# Schematic_4_22_12.net
KiCad netlist of a schematic drawn in EAGLE
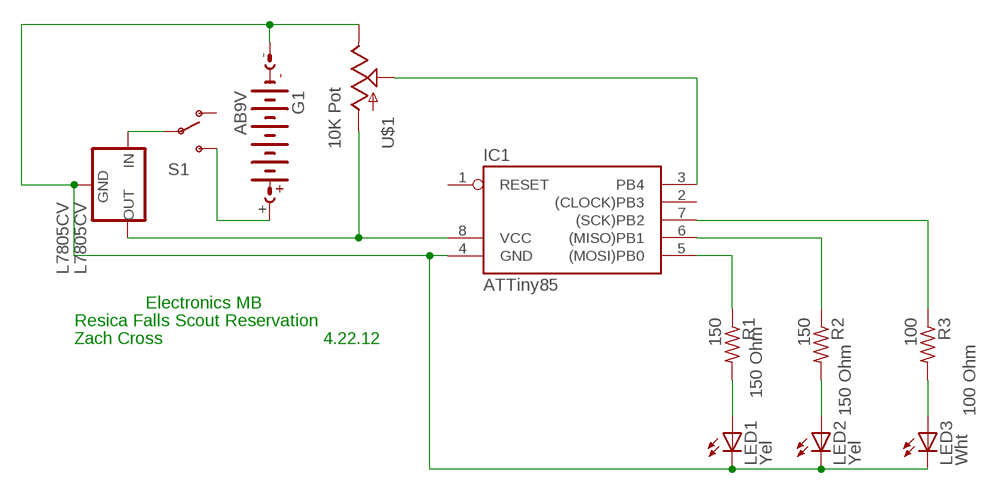
[diagram p0: schematic, sheet 1]

(export (version "E")
  (design (tool "Eeschema 10.0.6"))
  (components
    (comp (ref "G1")
      (value "AB9V")
      (footprint "eagle-import:AB9V")
      (libsource (lib "eagle-import") (part "AB9V"))
    )
    (comp (ref "IC1")
      (value "ATTiny85")
      (footprint "eagle-import:DIL08")
      (libsource (lib "eagle-import") (part "TINY22P"))
    )
    (comp (ref "L7805CV")
      (value "L7805CV")
      (footprint "eagle-import:78XXL")
      (libsource (lib "eagle-import") (part "V_REG_78XXSIDE"))
    )
    (comp (ref "LED1")
      (value "Yel")
      (footprint "eagle-import:LED5MM")
      (fields (field (name "COLOR") "Yellow"))
      (libsource (lib "eagle-import") (part "LED5MM"))
    )
    (comp (ref "LED2")
      (value "Yel")
      (footprint "eagle-import:LED5MM")
      (fields (field (name "COLOR") "Yellow"))
      (libsource (lib "eagle-import") (part "LED5MM"))
    )
    (comp (ref "LED3")
      (value "Wht")
      (footprint "eagle-import:LED5MM")
      (fields (field (name "COLOR") "White"))
      (libsource (lib "eagle-import") (part "LED5MM"))
    )
    (comp (ref "R1")
      (value "150")
      (footprint "eagle-import:0204_7")
      (fields (field (name "RESISTANCE") "150 Ohm"))
      (libsource (lib "eagle-import") (part "R-US_0204/7"))
    )
    (comp (ref "R2")
      (value "150")
      (footprint "eagle-import:0204_7")
      (fields (field (name "RESISTANCE") "150 Ohm"))
      (libsource (lib "eagle-import") (part "R-US_0204/7"))
    )
    (comp (ref "R3")
      (value "100")
      (footprint "eagle-import:0204_7")
      (fields (field (name "RESISTANCE") "100 Ohm"))
      (libsource (lib "eagle-import") (part "R-US_0204/7"))
    )
    (comp (ref "S1")
      (value "SWITCH-SPSTPTH")
      (footprint "eagle-import:SWITCH-SPDT")
      (libsource (lib "eagle-import") (part "SWITCH-SPSTPTH"))
    )
    (comp (ref "U$1")
      (value "10K Pot")
      (footprint "eagle-import:ALPS_POT")
      (libsource (lib "eagle-import") (part "POT"))
    )
  )
  (nets
    (net (code "1") (name "Net-(IC1-(MISO)PB1)") (class "Default")
      (node (ref "IC1") (pin "6") (pinfunction "(MISO)PB1_6") (pintype "bidirectional"))
      (node (ref "R2") (pin "1") (pinfunction "1_1") (pintype "passive"))
    )
    (net (code "2") (name "Net-(IC1-(MOSI)PB0)") (class "Default")
      (node (ref "IC1") (pin "5") (pinfunction "(MOSI)PB0_5") (pintype "bidirectional"))
      (node (ref "R1") (pin "1") (pinfunction "1_1") (pintype "passive"))
    )
    (net (code "3") (name "Net-(IC1-(SCK)PB2)") (class "Default")
      (node (ref "IC1") (pin "7") (pinfunction "(SCK)PB2_7") (pintype "bidirectional"))
      (node (ref "R3") (pin "1") (pinfunction "1_1") (pintype "passive"))
    )
    (net (code "4") (name "Net-(IC1-GND)") (class "Default")
      (node (ref "G1") (pin "-") (pinfunction "-_-") (pintype "passive"))
      (node (ref "IC1") (pin "4") (pinfunction "GND_4") (pintype "power_in"))
      (node (ref "L7805CV") (pin "GND") (pinfunction "GND_GND") (pintype "input"))
      (node (ref "LED1") (pin "K") (pinfunction "C_K") (pintype "passive"))
      (node (ref "LED2") (pin "K") (pinfunction "C_K") (pintype "passive"))
      (node (ref "LED3") (pin "K") (pinfunction "C_K") (pintype "passive"))
      (node (ref "U$1") (pin "P$1") (pinfunction "E_P$1") (pintype "passive"))
    )
    (net (code "5") (name "Net-(IC1-PB4)") (class "Default")
      (node (ref "IC1") (pin "3") (pinfunction "PB4_3") (pintype "bidirectional"))
      (node (ref "U$1") (pin "P$2") (pinfunction "S_P$2") (pintype "passive"))
    )
    (net (code "6") (name "Net-(IC1-VCC)") (class "Default")
      (node (ref "IC1") (pin "8") (pinfunction "VCC_8") (pintype "power_in"))
      (node (ref "L7805CV") (pin "OUT") (pinfunction "OUT_OUT") (pintype "output"))
      (node (ref "U$1") (pin "P$3") (pinfunction "A_P$3") (pintype "passive"))
    )
    (net (code "7") (name "Net-(LED1-PadA)") (class "Default")
      (node (ref "LED1") (pin "A") (pinfunction "A_A") (pintype "passive"))
      (node (ref "R1") (pin "2") (pinfunction "2_2") (pintype "passive"))
    )
    (net (code "8") (name "Net-(LED2-PadA)") (class "Default")
      (node (ref "LED2") (pin "A") (pinfunction "A_A") (pintype "passive"))
      (node (ref "R2") (pin "2") (pinfunction "2_2") (pintype "passive"))
    )
    (net (code "9") (name "Net-(LED3-PadA)") (class "Default")
      (node (ref "LED3") (pin "A") (pinfunction "A_A") (pintype "passive"))
      (node (ref "R3") (pin "2") (pinfunction "2_2") (pintype "passive"))
    )
    (net (code "10") (name "Net-(S1-P)") (class "Default")
      (node (ref "L7805CV") (pin "IN") (pinfunction "IN_IN") (pintype "input"))
      (node (ref "S1") (pin "2") (pinfunction "P_2") (pintype "passive"))
    )
    (net (code "11") (name "Net-(S1-S)") (class "Default")
      (node (ref "G1") (pin "+") (pinfunction "+_+") (pintype "passive"))
      (node (ref "S1") (pin "3") (pinfunction "S_3") (pintype "passive"))
    )
    (net (code "12") (name "unconnected-(IC1-(CLOCK)PB3-Pad2)") (class "Default")
      (node (ref "IC1") (pin "2") (pinfunction "(CLOCK)PB3_2") (pintype "bidirectional"))
    )
    (net (code "13") (name "unconnected-(IC1-RESET-Pad1)") (class "Default")
      (node (ref "IC1") (pin "1") (pinfunction "RESET_1") (pintype "input"))
    )
    (net (code "14") (name "unconnected-(S1-O-Pad1)") (class "Default")
      (node (ref "S1") (pin "1") (pinfunction "O_1") (pintype "passive"))
    )
  )
)
